# ArduinoUno_Rpi.net
KiCad netlist of a schematic drawn in Altium Designer
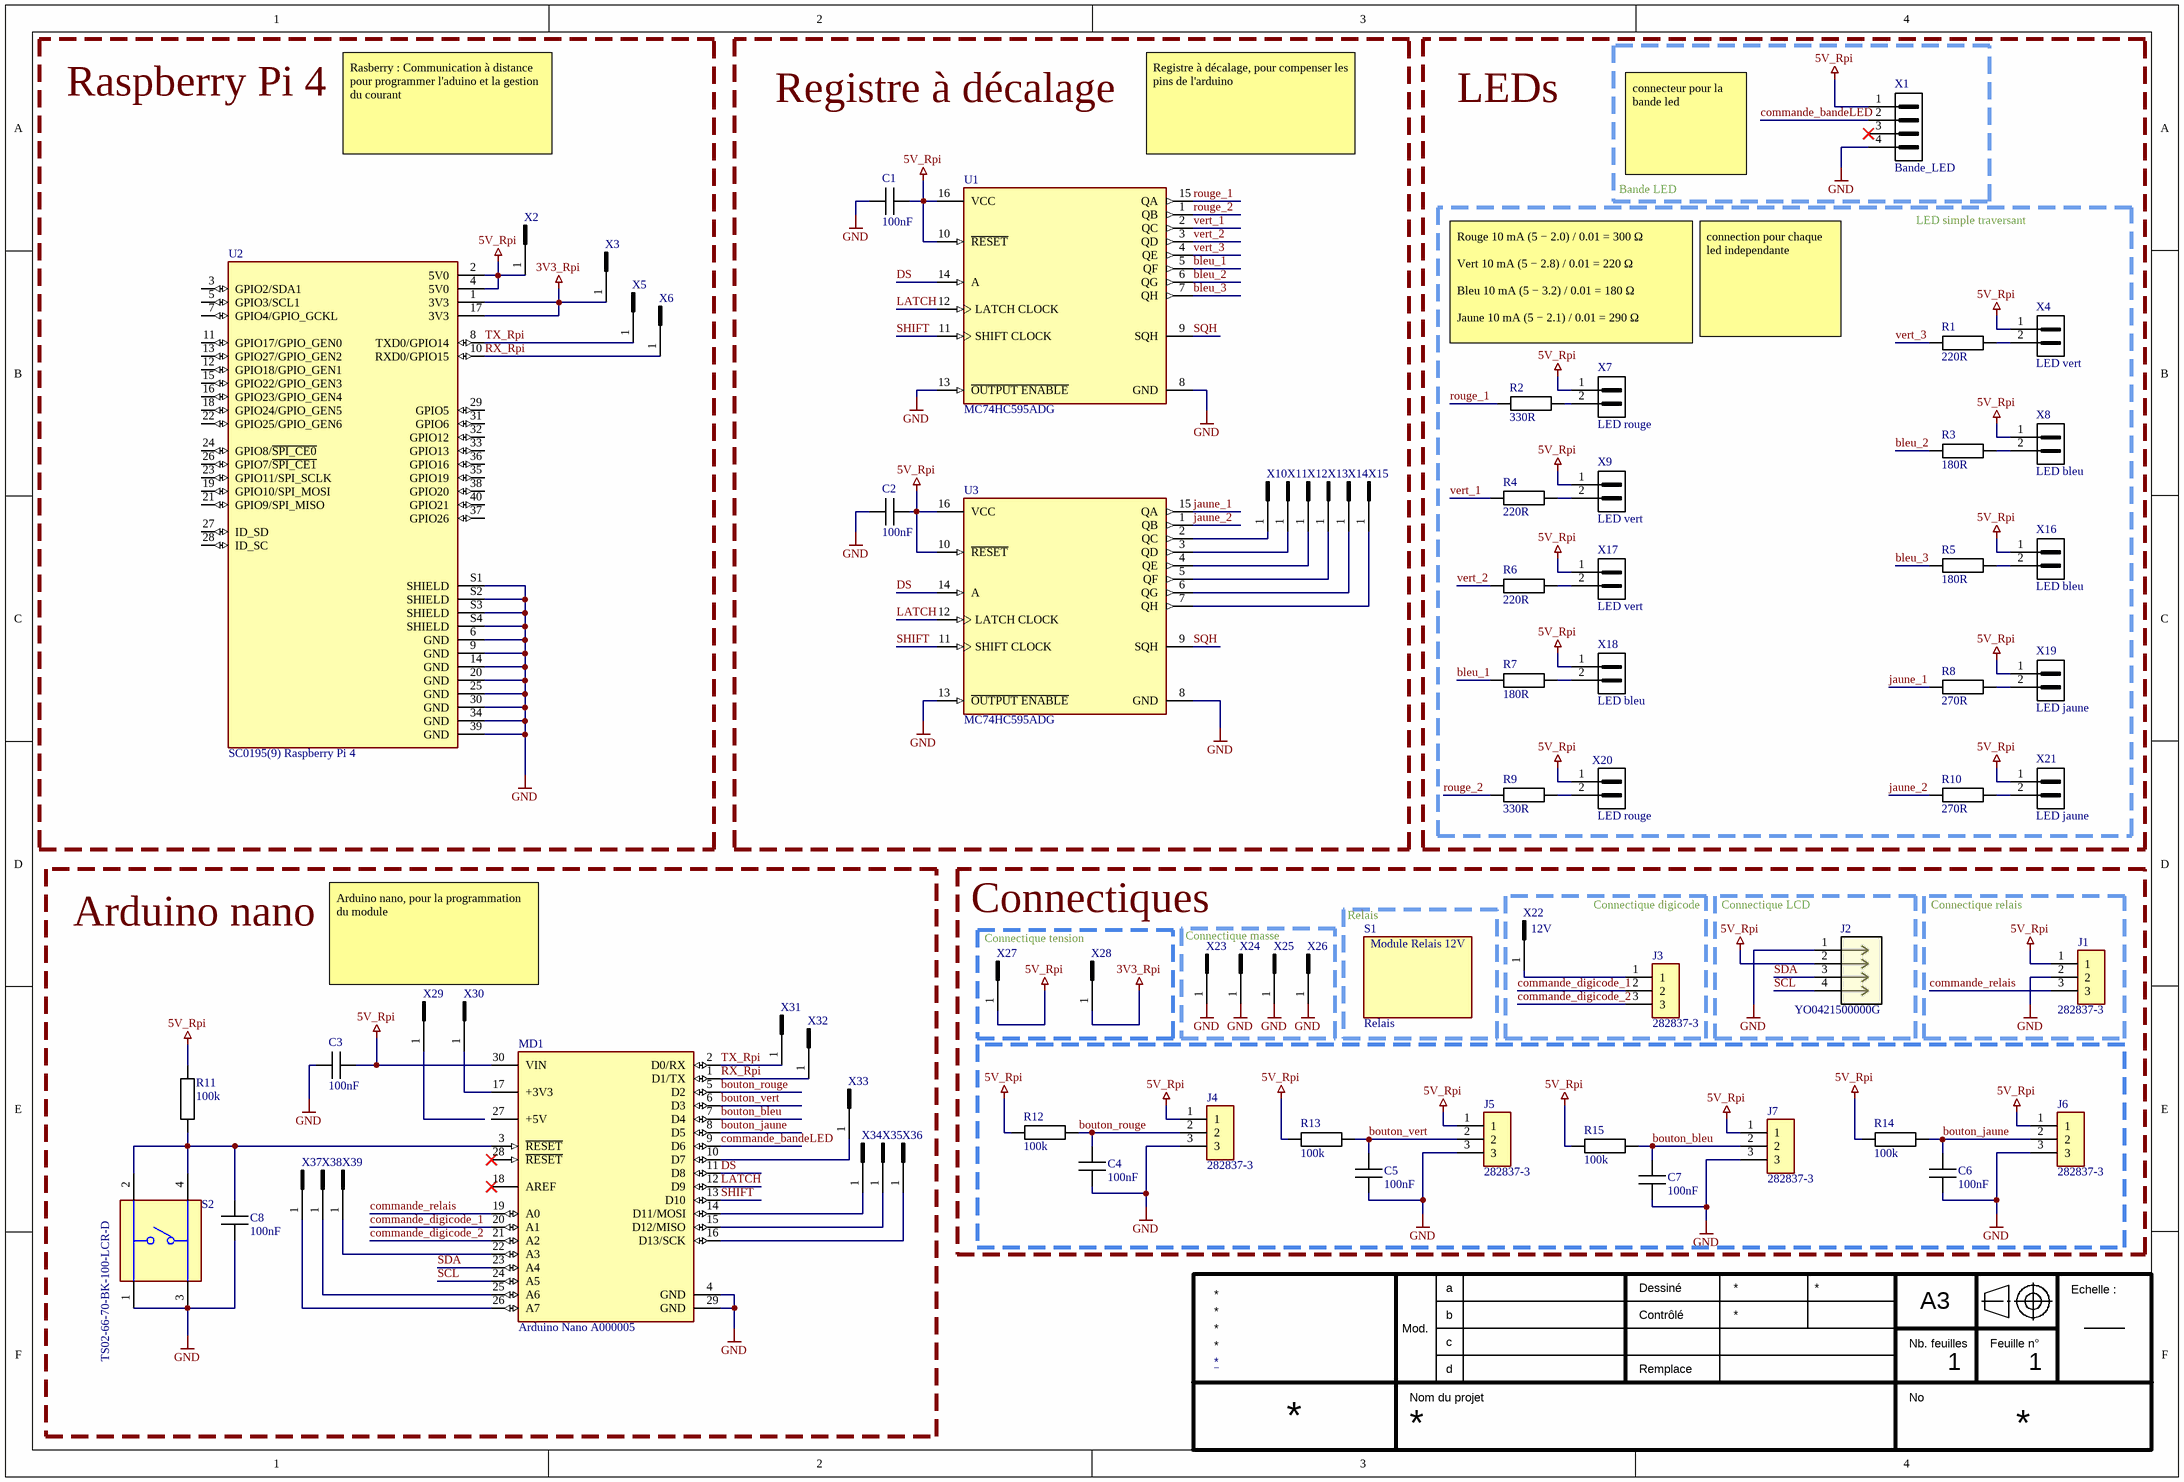
[diagram p0: ArduinoUno_Rpi.SchDoc]

(export (version "E")
  (design (tool "Eeschema 10.0.6"))
  (components
    (comp (ref "C1")
      (value "100nF")
      (footprint "CAPC2012X08M")
      (description "CAPC 100nF X7R 50V 10% 2012 (0805 INCH)")
      (fields (field (name "VOLTAGE") "50V") (field (name "MANUFACTURER") "TDK"))
      (libsource (lib "ETML-ES") (part "CAP"))
    )
    (comp (ref "C2")
      (value "100nF")
      (footprint "CAPC2012X08M")
      (description "CAPC 100nF X7R 50V 10% 2012 (0805 INCH)")
      (fields (field (name "VOLTAGE") "50V") (field (name "MANUFACTURER") "TDK"))
      (libsource (lib "ETML-ES") (part "CAP"))
    )
    (comp (ref "C3")
      (value "100nF")
      (footprint "CAPC2012X08M")
      (description "CAPC 100nF X7R 50V 10% 2012 (0805 INCH)")
      (fields (field (name "VOLTAGE") "50V") (field (name "MANUFACTURER") "TDK"))
      (libsource (lib "ETML-ES") (part "CAP"))
    )
    (comp (ref "C4")
      (value "100nF")
      (footprint "CAPC2012X08M")
      (description "CAPC 100nF X7R 50V 10% 2012 (0805 INCH)")
      (fields (field (name "VOLTAGE") "50V") (field (name "MANUFACTURER") "TDK"))
      (libsource (lib "ETML-ES") (part "CAP"))
    )
    (comp (ref "C5")
      (value "100nF")
      (footprint "CAPC2012X08M")
      (description "CAPC 100nF X7R 50V 10% 2012 (0805 INCH)")
      (fields (field (name "VOLTAGE") "50V") (field (name "MANUFACTURER") "TDK"))
      (libsource (lib "ETML-ES") (part "CAP"))
    )
    (comp (ref "C6")
      (value "100nF")
      (footprint "CAPC2012X08M")
      (description "CAPC 100nF X7R 50V 10% 2012 (0805 INCH)")
      (fields (field (name "VOLTAGE") "50V") (field (name "MANUFACTURER") "TDK"))
      (libsource (lib "ETML-ES") (part "CAP"))
    )
    (comp (ref "C7")
      (value "100nF")
      (footprint "CAPC2012X08M")
      (description "CAPC 100nF X7R 50V 10% 2012 (0805 INCH)")
      (fields (field (name "VOLTAGE") "50V") (field (name "MANUFACTURER") "TDK"))
      (libsource (lib "ETML-ES") (part "CAP"))
    )
    (comp (ref "C8")
      (value "100nF")
      (footprint "CAPC2012X08M")
      (description "CAPC 100nF X7R 50V 10% 2012 (0805 INCH)")
      (fields (field (name "VOLTAGE") "50V") (field (name "MANUFACTURER") "TDK"))
      (libsource (lib "ETML-ES") (part "CAP"))
    )
    (comp (ref "J1")
      (value "282837-3")
      (footprint "TE_282837-3")
      (description "TERMI-BLOK PCB MOUNT 3P")
      (libsource (lib "Schlib1") (part "282837-3"))
    )
    (comp (ref "J2")
      (value "YO0421500000G")
      (footprint "CONN4_500000G_AMP")
      (description "No Description Available")
      (fields (field (name "COPYRIGHT") "Copyright (C) 2025 Ultra Librarian. All rights reserved."))
      (libsource (lib "Schlib1") (part "YO0421500000G"))
    )
    (comp (ref "J3")
      (value "282837-3")
      (footprint "TE_282837-3")
      (description "TERMI-BLOK PCB MOUNT 3P")
      (libsource (lib "Schlib1") (part "282837-3"))
    )
    (comp (ref "J4")
      (value "282837-3")
      (footprint "TE_282837-3")
      (description "TERMI-BLOK PCB MOUNT 3P")
      (libsource (lib "Schlib1") (part "282837-3"))
    )
    (comp (ref "J5")
      (value "282837-3")
      (footprint "TE_282837-3")
      (description "TERMI-BLOK PCB MOUNT 3P")
      (libsource (lib "Schlib1") (part "282837-3"))
    )
    (comp (ref "J6")
      (value "282837-3")
      (footprint "TE_282837-3")
      (description "TERMI-BLOK PCB MOUNT 3P")
      (libsource (lib "Schlib1") (part "282837-3"))
    )
    (comp (ref "J7")
      (value "282837-3")
      (footprint "TE_282837-3")
      (description "TERMI-BLOK PCB MOUNT 3P")
      (libsource (lib "Schlib1") (part "282837-3"))
    )
    (comp (ref "MD1")
      (value "Arduino Nano A000005")
      (footprint "FP-A000005-MFG")
      (description "ARDUINO NANO ATMEGA328 EVAL BRD")
      (libsource (lib "Altium Content Vault") (part "d190c066e99afd1c6882cf92e11b2cc"))
    )
    (comp (ref "R1")
      (value "220R")
      (footprint "RESC1608X06M")
      (description "RES 220ohm  ±1% 0.1W  1608 (0603 INCH)")
      (fields (field (name "POWER") "0.1W") (field (name "VOLTAGE") "75V"))
      (libsource (lib "ETML-ES") (part "RES"))
    )
    (comp (ref "R2")
      (value "330R")
      (footprint "RESC1608X06M")
      (description "RES 330ohm  ±1% 0.1W  1608 (0603 INCH)")
      (fields (field (name "TOLERANCE") "±1%") (field (name "VOLTAGE") "75V"))
      (libsource (lib "ETML-ES") (part "RES"))
    )
    (comp (ref "R3")
      (value "180R")
      (footprint "RESC1608X06M")
      (description "RES 180ohm  ±1% 0.1W  1608 (0603 INCH)")
      (fields (field (name "TOLERANCE") "±1%") (field (name "VOLTAGE") "75V"))
      (libsource (lib "ETML-ES") (part "RES"))
    )
    (comp (ref "R4")
      (value "220R")
      (footprint "RESC1608X06M")
      (description "RES 220ohm  ±1% 0.1W  1608 (0603 INCH)")
      (fields (field (name "POWER") "0.1W") (field (name "VOLTAGE") "75V"))
      (libsource (lib "ETML-ES") (part "RES"))
    )
    (comp (ref "R5")
      (value "180R")
      (footprint "RESC1608X06M")
      (description "RES 180ohm  ±1% 0.1W  1608 (0603 INCH)")
      (fields (field (name "TOLERANCE") "±1%") (field (name "VOLTAGE") "75V"))
      (libsource (lib "ETML-ES") (part "RES"))
    )
    (comp (ref "R6")
      (value "220R")
      (footprint "RESC1608X06M")
      (description "RES 220ohm  ±1% 0.1W  1608 (0603 INCH)")
      (fields (field (name "POWER") "0.1W") (field (name "VOLTAGE") "75V"))
      (libsource (lib "ETML-ES") (part "RES"))
    )
    (comp (ref "R7")
      (value "180R")
      (footprint "RESC1608X06M")
      (description "RES 180ohm  ±1% 0.1W  1608 (0603 INCH)")
      (fields (field (name "TOLERANCE") "±1%") (field (name "VOLTAGE") "75V"))
      (libsource (lib "ETML-ES") (part "RES"))
    )
    (comp (ref "R8")
      (value "270R")
      (footprint "RESC1608X06M")
      (description "RES 270ohm  ±1% 0.1W  1608 (0603 INCH)")
      (fields (field (name "TOLERANCE") "±1%") (field (name "MANUFACTURER") "Yageo"))
      (libsource (lib "ETML-ES") (part "RES"))
    )
    (comp (ref "R9")
      (value "330R")
      (footprint "RESC1608X06M")
      (description "RES 330ohm  ±1% 0.1W  1608 (0603 INCH)")
      (fields (field (name "TOLERANCE") "±1%") (field (name "VOLTAGE") "75V"))
      (libsource (lib "ETML-ES") (part "RES"))
    )
    (comp (ref "R10")
      (value "270R")
      (footprint "RESC1608X06M")
      (description "RES 270ohm  ±1% 0.1W  1608 (0603 INCH)")
      (fields (field (name "TOLERANCE") "±1%") (field (name "MANUFACTURER") "Yageo"))
      (libsource (lib "ETML-ES") (part "RES"))
    )
    (comp (ref "R11")
      (value "100k")
      (footprint "RESC2012X06M")
      (description "RES 100kohm  ±1% 0.125W 2012 (0805 INCH)")
      (fields (field (name "MANUFACTURER") "Yageo") (field (name "VOLTAGE") "150V"))
      (libsource (lib "ETML-ES") (part "RES"))
    )
    (comp (ref "R12")
      (value "100k")
      (footprint "RESC2012X06M")
      (description "RES 100kohm  ±1% 0.125W 2012 (0805 INCH)")
      (fields (field (name "MANUFACTURER") "Yageo") (field (name "VOLTAGE") "150V"))
      (libsource (lib "ETML-ES") (part "RES"))
    )
    (comp (ref "R13")
      (value "100k")
      (footprint "RESC2012X06M")
      (description "RES 100kohm  ±1% 0.125W 2012 (0805 INCH)")
      (fields (field (name "MANUFACTURER") "Yageo") (field (name "VOLTAGE") "150V"))
      (libsource (lib "ETML-ES") (part "RES"))
    )
    (comp (ref "R14")
      (value "100k")
      (footprint "RESC2012X06M")
      (description "RES 100kohm  ±1% 0.125W 2012 (0805 INCH)")
      (fields (field (name "MANUFACTURER") "Yageo") (field (name "VOLTAGE") "150V"))
      (libsource (lib "ETML-ES") (part "RES"))
    )
    (comp (ref "R15")
      (value "100k")
      (footprint "RESC2012X06M")
      (description "RES 100kohm  ±1% 0.125W 2012 (0805 INCH)")
      (fields (field (name "MANUFACTURER") "Yageo") (field (name "VOLTAGE") "150V"))
      (libsource (lib "ETML-ES") (part "RES"))
    )
    (comp (ref "S1")
      (value "Relais")
      (footprint "BOOSTER12V")
      (description "6 x 6 mm, 7 mm Actuator Height, 100 gf, Black, Long Crimped, Through Hole, SPST, Tactile Switch")
      (fields (field (name "MF") "Same Sky") (field (name "MP") "TS02-66-70-BK-100-LCR-D"))
      (libsource (lib "Schlib1") (part "Relais"))
    )
    (comp (ref "S2")
      (value "TS02-66-70-BK-100-LCR-D")
      (footprint "SW_TS02-66-70-BK-100-LCR-D")
      (description "6 x 6 mm, 7 mm Actuator Height, 100 gf, Black, Long Crimped, Through Hole, SPST, Tactile Switch")
      (fields (field (name "MF") "Same Sky"))
      (libsource (lib "Schlib1") (part "TS02-66-70-BK-100-LCR-D"))
    )
    (comp (ref "U1")
      (value "MC74HC595ADG")
      (footprint "FP-751B-05-MFG")
      (description "IC SHIFT REGISTER 8BIT 16-SOIC")
      (fields
        (field (name "MANUFACTURER") "On Semiconductor")
        (field (name "OCTOPART") "https://octopart.com/mc74hc595adg-on+semiconductor-127876")
      )
      (libsource (lib "Altium Content Vault") (part "e046d8e229ee38add04da4060949ea7"))
    )
    (comp (ref "U2")
      (value "SC0195(9) Raspberry Pi 4")
      (footprint "MODULE_SC0195(9)")
      (fields (field (name "MF") "Raspberry Pi") (field (name "MP") "SC0195(9)"))
      (libsource (lib "Schlib1") (part "SC0195(9)"))
    )
    (comp (ref "U3")
      (value "MC74HC595ADG")
      (footprint "FP-751B-05-MFG")
      (description "IC SHIFT REGISTER 8BIT 16-SOIC")
      (fields
        (field (name "MANUFACTURER") "On Semiconductor")
        (field (name "OCTOPART") "https://octopart.com/mc74hc595adg-on+semiconductor-127876")
      )
      (libsource (lib "Altium Content Vault") (part "e046d8e229ee38add04da4060949ea7"))
    )
    (comp (ref "X1")
      (value "Bande_LED")
      (footprint "PIN-1x04-2.54")
      (description "PIN HEADER 2.54 1x04")
      (fields (field (name "MANUFACTURER") "Würth Electronik") (field (name "VOLTAGE") "250V"))
      (libsource (lib "ETML-ES") (part "CON-PIN-1x04"))
    )
    (comp (ref "X2")
      (value "2.54")
      (footprint "PIN-1x01-2.54")
      (description "PIN HEADER 2.54 1x01")
      (fields (field (name "VOLTAGE") "250V") (field (name "MANUFACTURER") "Würth Electronik"))
      (libsource (lib "ETML-ES") (part "CON-PIN-1x01"))
    )
    (comp (ref "X3")
      (value "2.54")
      (footprint "PIN-1x01-2.54")
      (description "PIN HEADER 2.54 1x01")
      (fields (field (name "VOLTAGE") "250V") (field (name "MANUFACTURER") "Würth Electronik"))
      (libsource (lib "ETML-ES") (part "CON-PIN-1x01"))
    )
    (comp (ref "X4")
      (value "LED vert")
      (footprint "PIN-1x02-2.54")
      (description "PIN HEADER 2.54 1x02")
      (fields (field (name "MANUFACTURER") "Würth Electronik") (field (name "VOLTAGE") "250V"))
      (libsource (lib "ETML-ES") (part "CON-PIN-1x02"))
    )
    (comp (ref "X5")
      (value "2.54")
      (footprint "PIN-1x01-2.54")
      (description "PIN HEADER 2.54 1x01")
      (fields (field (name "VOLTAGE") "250V") (field (name "MANUFACTURER") "Würth Electronik"))
      (libsource (lib "ETML-ES") (part "CON-PIN-1x01"))
    )
    (comp (ref "X6")
      (value "2.54")
      (footprint "PIN-1x01-2.54")
      (description "PIN HEADER 2.54 1x01")
      (fields (field (name "VOLTAGE") "250V") (field (name "MANUFACTURER") "Würth Electronik"))
      (libsource (lib "ETML-ES") (part "CON-PIN-1x01"))
    )
    (comp (ref "X7")
      (value "LED rouge")
      (footprint "PIN-1x02-2.54")
      (description "PIN HEADER 2.54 1x02")
      (fields (field (name "MANUFACTURER") "Würth Electronik") (field (name "VOLTAGE") "250V"))
      (libsource (lib "ETML-ES") (part "CON-PIN-1x02"))
    )
    (comp (ref "X8")
      (value "LED bleu")
      (footprint "PIN-1x02-2.54")
      (description "PIN HEADER 2.54 1x02")
      (fields (field (name "MANUFACTURER") "Würth Electronik") (field (name "VOLTAGE") "250V"))
      (libsource (lib "ETML-ES") (part "CON-PIN-1x02"))
    )
    (comp (ref "X9")
      (value "LED vert")
      (footprint "PIN-1x02-2.54")
      (description "PIN HEADER 2.54 1x02")
      (fields (field (name "MANUFACTURER") "Würth Electronik") (field (name "VOLTAGE") "250V"))
      (libsource (lib "ETML-ES") (part "CON-PIN-1x02"))
    )
    (comp (ref "X10")
      (value "2.54")
      (footprint "PIN-1x01-2.54")
      (description "PIN HEADER 2.54 1x01")
      (fields (field (name "VOLTAGE") "250V") (field (name "MANUFACTURER") "Würth Electronik"))
      (libsource (lib "ETML-ES") (part "CON-PIN-1x01"))
    )
    (comp (ref "X11")
      (value "2.54")
      (footprint "PIN-1x01-2.54")
      (description "PIN HEADER 2.54 1x01")
      (fields (field (name "VOLTAGE") "250V") (field (name "MANUFACTURER") "Würth Electronik"))
      (libsource (lib "ETML-ES") (part "CON-PIN-1x01"))
    )
    (comp (ref "X12")
      (value "2.54")
      (footprint "PIN-1x01-2.54")
      (description "PIN HEADER 2.54 1x01")
      (fields (field (name "VOLTAGE") "250V") (field (name "MANUFACTURER") "Würth Electronik"))
      (libsource (lib "ETML-ES") (part "CON-PIN-1x01"))
    )
    (comp (ref "X13")
      (value "2.54")
      (footprint "PIN-1x01-2.54")
      (description "PIN HEADER 2.54 1x01")
      (fields (field (name "VOLTAGE") "250V") (field (name "MANUFACTURER") "Würth Electronik"))
      (libsource (lib "ETML-ES") (part "CON-PIN-1x01"))
    )
    (comp (ref "X14")
      (value "2.54")
      (footprint "PIN-1x01-2.54")
      (description "PIN HEADER 2.54 1x01")
      (fields (field (name "VOLTAGE") "250V") (field (name "MANUFACTURER") "Würth Electronik"))
      (libsource (lib "ETML-ES") (part "CON-PIN-1x01"))
    )
    (comp (ref "X15")
      (value "2.54")
      (footprint "PIN-1x01-2.54")
      (description "PIN HEADER 2.54 1x01")
      (fields (field (name "VOLTAGE") "250V") (field (name "MANUFACTURER") "Würth Electronik"))
      (libsource (lib "ETML-ES") (part "CON-PIN-1x01"))
    )
    (comp (ref "X16")
      (value "LED bleu")
      (footprint "PIN-1x02-2.54")
      (description "PIN HEADER 2.54 1x02")
      (fields (field (name "MANUFACTURER") "Würth Electronik") (field (name "VOLTAGE") "250V"))
      (libsource (lib "ETML-ES") (part "CON-PIN-1x02"))
    )
    (comp (ref "X17")
      (value "LED vert")
      (footprint "PIN-1x02-2.54")
      (description "PIN HEADER 2.54 1x02")
      (fields (field (name "MANUFACTURER") "Würth Electronik") (field (name "VOLTAGE") "250V"))
      (libsource (lib "ETML-ES") (part "CON-PIN-1x02"))
    )
    (comp (ref "X18")
      (value "LED bleu")
      (footprint "PIN-1x02-2.54")
      (description "PIN HEADER 2.54 1x02")
      (fields (field (name "MANUFACTURER") "Würth Electronik") (field (name "VOLTAGE") "250V"))
      (libsource (lib "ETML-ES") (part "CON-PIN-1x02"))
    )
    (comp (ref "X19")
      (value "LED jaune")
      (footprint "PIN-1x02-2.54")
      (description "PIN HEADER 2.54 1x02")
      (fields (field (name "MANUFACTURER") "Würth Electronik") (field (name "VOLTAGE") "250V"))
      (libsource (lib "ETML-ES") (part "CON-PIN-1x02"))
    )
    (comp (ref "X20")
      (value "LED rouge")
      (footprint "PIN-1x02-2.54")
      (description "PIN HEADER 2.54 1x02")
      (fields (field (name "MANUFACTURER") "Würth Electronik") (field (name "VOLTAGE") "250V"))
      (libsource (lib "ETML-ES") (part "CON-PIN-1x02"))
    )
    (comp (ref "X21")
      (value "LED jaune")
      (footprint "PIN-1x02-2.54")
      (description "PIN HEADER 2.54 1x02")
      (fields (field (name "MANUFACTURER") "Würth Electronik") (field (name "VOLTAGE") "250V"))
      (libsource (lib "ETML-ES") (part "CON-PIN-1x02"))
    )
    (comp (ref "X22")
      (value "12V")
      (footprint "PIN-1x01-2.54")
      (description "PIN HEADER 2.54 1x01")
      (fields (field (name "VOLTAGE") "250V") (field (name "MANUFACTURER") "Würth Electronik"))
      (libsource (lib "ETML-ES") (part "CON-PIN-1x01"))
    )
    (comp (ref "X23")
      (value "2.54")
      (footprint "PIN-1x01-2.54")
      (description "PIN HEADER 2.54 1x01")
      (fields (field (name "VOLTAGE") "250V") (field (name "MANUFACTURER") "Würth Electronik"))
      (libsource (lib "ETML-ES") (part "CON-PIN-1x01"))
    )
    (comp (ref "X24")
      (value "2.54")
      (footprint "PIN-1x01-2.54")
      (description "PIN HEADER 2.54 1x01")
      (fields (field (name "VOLTAGE") "250V") (field (name "MANUFACTURER") "Würth Electronik"))
      (libsource (lib "ETML-ES") (part "CON-PIN-1x01"))
    )
    (comp (ref "X25")
      (value "2.54")
      (footprint "PIN-1x01-2.54")
      (description "PIN HEADER 2.54 1x01")
      (fields (field (name "VOLTAGE") "250V") (field (name "MANUFACTURER") "Würth Electronik"))
      (libsource (lib "ETML-ES") (part "CON-PIN-1x01"))
    )
    (comp (ref "X26")
      (value "2.54")
      (footprint "PIN-1x01-2.54")
      (description "PIN HEADER 2.54 1x01")
      (fields (field (name "VOLTAGE") "250V") (field (name "MANUFACTURER") "Würth Electronik"))
      (libsource (lib "ETML-ES") (part "CON-PIN-1x01"))
    )
    (comp (ref "X27")
      (value "2.54")
      (footprint "PIN-1x01-2.54")
      (description "PIN HEADER 2.54 1x01")
      (fields (field (name "VOLTAGE") "250V") (field (name "MANUFACTURER") "Würth Electronik"))
      (libsource (lib "ETML-ES") (part "CON-PIN-1x01"))
    )
    (comp (ref "X28")
      (value "2.54")
      (footprint "PIN-1x01-2.54")
      (description "PIN HEADER 2.54 1x01")
      (fields (field (name "VOLTAGE") "250V") (field (name "MANUFACTURER") "Würth Electronik"))
      (libsource (lib "ETML-ES") (part "CON-PIN-1x01"))
    )
    (comp (ref "X29")
      (value "2.54")
      (footprint "PIN-1x01-2.54")
      (description "PIN HEADER 2.54 1x01")
      (fields (field (name "VOLTAGE") "250V") (field (name "MANUFACTURER") "Würth Electronik"))
      (libsource (lib "ETML-ES") (part "CON-PIN-1x01"))
    )
    (comp (ref "X30")
      (value "2.54")
      (footprint "PIN-1x01-2.54")
      (description "PIN HEADER 2.54 1x01")
      (fields (field (name "VOLTAGE") "250V") (field (name "MANUFACTURER") "Würth Electronik"))
      (libsource (lib "ETML-ES") (part "CON-PIN-1x01"))
    )
    (comp (ref "X31")
      (value "2.54")
      (footprint "PIN-1x01-2.54")
      (description "PIN HEADER 2.54 1x01")
      (fields (field (name "VOLTAGE") "250V") (field (name "MANUFACTURER") "Würth Electronik"))
      (libsource (lib "ETML-ES") (part "CON-PIN-1x01"))
    )
    (comp (ref "X32")
      (value "2.54")
      (footprint "PIN-1x01-2.54")
      (description "PIN HEADER 2.54 1x01")
      (fields (field (name "VOLTAGE") "250V") (field (name "MANUFACTURER") "Würth Electronik"))
      (libsource (lib "ETML-ES") (part "CON-PIN-1x01"))
    )
    (comp (ref "X33")
      (value "2.54")
      (footprint "PIN-1x01-2.54")
      (description "PIN HEADER 2.54 1x01")
      (fields (field (name "VOLTAGE") "250V") (field (name "MANUFACTURER") "Würth Electronik"))
      (libsource (lib "ETML-ES") (part "CON-PIN-1x01"))
    )
    (comp (ref "X34")
      (value "2.54")
      (footprint "PIN-1x01-2.54")
      (description "PIN HEADER 2.54 1x01")
      (fields (field (name "VOLTAGE") "250V") (field (name "MANUFACTURER") "Würth Electronik"))
      (libsource (lib "ETML-ES") (part "CON-PIN-1x01"))
    )
    (comp (ref "X35")
      (value "2.54")
      (footprint "PIN-1x01-2.54")
      (description "PIN HEADER 2.54 1x01")
      (fields (field (name "VOLTAGE") "250V") (field (name "MANUFACTURER") "Würth Electronik"))
      (libsource (lib "ETML-ES") (part "CON-PIN-1x01"))
    )
    (comp (ref "X36")
      (value "2.54")
      (footprint "PIN-1x01-2.54")
      (description "PIN HEADER 2.54 1x01")
      (fields (field (name "VOLTAGE") "250V") (field (name "MANUFACTURER") "Würth Electronik"))
      (libsource (lib "ETML-ES") (part "CON-PIN-1x01"))
    )
    (comp (ref "X37")
      (value "2.54")
      (footprint "PIN-1x01-2.54")
      (description "PIN HEADER 2.54 1x01")
      (fields (field (name "VOLTAGE") "250V") (field (name "MANUFACTURER") "Würth Electronik"))
      (libsource (lib "ETML-ES") (part "CON-PIN-1x01"))
    )
    (comp (ref "X38")
      (value "2.54")
      (footprint "PIN-1x01-2.54")
      (description "PIN HEADER 2.54 1x01")
      (fields (field (name "VOLTAGE") "250V") (field (name "MANUFACTURER") "Würth Electronik"))
      (libsource (lib "ETML-ES") (part "CON-PIN-1x01"))
    )
    (comp (ref "X39")
      (value "2.54")
      (footprint "PIN-1x01-2.54")
      (description "PIN HEADER 2.54 1x01")
      (fields (field (name "VOLTAGE") "250V") (field (name "MANUFACTURER") "Würth Electronik"))
      (libsource (lib "ETML-ES") (part "CON-PIN-1x01"))
    )
  )
  (nets
    (net (code "1") (name "/DS") (class "Default")
      (node (ref "MD1") (pin "11") (pinfunction "D8_11") (pintype "bidirectional"))
      (node (ref "U1") (pin "14") (pinfunction "A_14") (pintype "input"))
      (node (ref "U3") (pin "14") (pinfunction "A_14") (pintype "input"))
    )
    (net (code "2") (name "/LATCH") (class "Default")
      (node (ref "MD1") (pin "12") (pinfunction "D9_12") (pintype "bidirectional"))
      (node (ref "U1") (pin "12") (pinfunction "LATCH_CLOCK_12") (pintype "input"))
      (node (ref "U3") (pin "12") (pinfunction "LATCH_CLOCK_12") (pintype "input"))
    )
    (net (code "3") (name "/RX_Rpi") (class "Default")
      (node (ref "MD1") (pin "1") (pinfunction "D1/TX_1") (pintype "bidirectional"))
      (node (ref "U2") (pin "10") (pinfunction "RXD0/GPIO15_10") (pintype "bidirectional"))
      (node (ref "X32") (pin "1") (pinfunction "1_1") (pintype "passive"))
      (node (ref "X6") (pin "1") (pinfunction "1_1") (pintype "passive"))
    )
    (net (code "4") (name "/SCL") (class "Default")
      (node (ref "J2") (pin "4") (pinfunction "4_4") (pintype "passive"))
      (node (ref "MD1") (pin "24") (pinfunction "A5_24") (pintype "bidirectional"))
    )
    (net (code "5") (name "/SDA") (class "Default")
      (node (ref "J2") (pin "3") (pinfunction "3_3") (pintype "passive"))
      (node (ref "MD1") (pin "23") (pinfunction "A4_23") (pintype "bidirectional"))
    )
    (net (code "6") (name "/SHIFT") (class "Default")
      (node (ref "MD1") (pin "13") (pinfunction "D10_13") (pintype "bidirectional"))
      (node (ref "U1") (pin "11") (pinfunction "SHIFT_CLOCK_11") (pintype "input"))
      (node (ref "U3") (pin "11") (pinfunction "SHIFT_CLOCK_11") (pintype "input"))
    )
    (net (code "7") (name "/SQH") (class "Default")
      (node (ref "U1") (pin "9") (pinfunction "SQH_9") (pintype "passive"))
      (node (ref "U3") (pin "9") (pinfunction "SQH_9") (pintype "passive"))
    )
    (net (code "8") (name "/TX_Rpi") (class "Default")
      (node (ref "MD1") (pin "2") (pinfunction "D0/RX_2") (pintype "bidirectional"))
      (node (ref "U2") (pin "8") (pinfunction "TXD0/GPIO14_8") (pintype "bidirectional"))
      (node (ref "X31") (pin "1") (pinfunction "1_1") (pintype "passive"))
      (node (ref "X5") (pin "1") (pinfunction "1_1") (pintype "passive"))
    )
    (net (code "9") (name "/bleu_1") (class "Default")
      (node (ref "R7") (pin "1") (pinfunction "1_1") (pintype "passive"))
      (node (ref "U1") (pin "5") (pinfunction "QF_5") (pintype "output"))
    )
    (net (code "10") (name "/bleu_2") (class "Default")
      (node (ref "R3") (pin "1") (pinfunction "1_1") (pintype "passive"))
      (node (ref "U1") (pin "6") (pinfunction "QG_6") (pintype "output"))
    )
    (net (code "11") (name "/bleu_3") (class "Default")
      (node (ref "R5") (pin "1") (pinfunction "1_1") (pintype "passive"))
      (node (ref "U1") (pin "7") (pinfunction "QH_7") (pintype "output"))
    )
    (net (code "12") (name "/bouton_bleu") (class "Default")
      (node (ref "C7") (pin "2") (pinfunction "2_2") (pintype "passive"))
      (node (ref "J7") (pin "2") (pinfunction "2_2") (pintype "passive"))
      (node (ref "MD1") (pin "7") (pinfunction "D4_7") (pintype "bidirectional"))
      (node (ref "R15") (pin "1") (pinfunction "1_1") (pintype "passive"))
    )
    (net (code "13") (name "/bouton_jaune") (class "Default")
      (node (ref "C6") (pin "2") (pinfunction "2_2") (pintype "passive"))
      (node (ref "J6") (pin "2") (pinfunction "2_2") (pintype "passive"))
      (node (ref "MD1") (pin "8") (pinfunction "D5_8") (pintype "bidirectional"))
      (node (ref "R14") (pin "1") (pinfunction "1_1") (pintype "passive"))
    )
    (net (code "14") (name "/bouton_rouge") (class "Default")
      (node (ref "C4") (pin "2") (pinfunction "2_2") (pintype "passive"))
      (node (ref "J4") (pin "2") (pinfunction "2_2") (pintype "passive"))
      (node (ref "MD1") (pin "5") (pinfunction "D2_5") (pintype "bidirectional"))
      (node (ref "R12") (pin "1") (pinfunction "1_1") (pintype "passive"))
    )
    (net (code "15") (name "/bouton_vert") (class "Default")
      (node (ref "C5") (pin "2") (pinfunction "2_2") (pintype "passive"))
      (node (ref "J5") (pin "2") (pinfunction "2_2") (pintype "passive"))
      (node (ref "MD1") (pin "6") (pinfunction "D3_6") (pintype "bidirectional"))
      (node (ref "R13") (pin "1") (pinfunction "1_1") (pintype "passive"))
    )
    (net (code "16") (name "/commande_bandeLED") (class "Default")
      (node (ref "MD1") (pin "9") (pinfunction "D6_9") (pintype "bidirectional"))
      (node (ref "X1") (pin "2") (pinfunction "2_2") (pintype "passive"))
    )
    (net (code "17") (name "/commande_digicode_1") (class "Default")
      (node (ref "J3") (pin "2") (pinfunction "2_2") (pintype "passive"))
      (node (ref "MD1") (pin "20") (pinfunction "A1_20") (pintype "bidirectional"))
    )
    (net (code "18") (name "/commande_digicode_2") (class "Default")
      (node (ref "J3") (pin "3") (pinfunction "3_3") (pintype "passive"))
      (node (ref "MD1") (pin "21") (pinfunction "A2_21") (pintype "bidirectional"))
    )
    (net (code "19") (name "/commande_relais") (class "Default")
      (node (ref "J1") (pin "3") (pinfunction "3_3") (pintype "passive"))
      (node (ref "MD1") (pin "19") (pinfunction "A0_19") (pintype "bidirectional"))
    )
    (net (code "20") (name "/jaune_1") (class "Default")
      (node (ref "R8") (pin "1") (pinfunction "1_1") (pintype "passive"))
      (node (ref "U3") (pin "15") (pinfunction "QA_15") (pintype "output"))
    )
    (net (code "21") (name "/jaune_2") (class "Default")
      (node (ref "R10") (pin "1") (pinfunction "1_1") (pintype "passive"))
      (node (ref "U3") (pin "1") (pinfunction "QB_1") (pintype "output"))
    )
    (net (code "22") (name "/rouge_1") (class "Default")
      (node (ref "R2") (pin "1") (pinfunction "1_1") (pintype "passive"))
      (node (ref "U1") (pin "15") (pinfunction "QA_15") (pintype "output"))
    )
    (net (code "23") (name "/rouge_2") (class "Default")
      (node (ref "R9") (pin "1") (pinfunction "1_1") (pintype "passive"))
      (node (ref "U1") (pin "1") (pinfunction "QB_1") (pintype "output"))
    )
    (net (code "24") (name "/vert_1") (class "Default")
      (node (ref "R4") (pin "1") (pinfunction "1_1") (pintype "passive"))
      (node (ref "U1") (pin "2") (pinfunction "QC_2") (pintype "output"))
    )
    (net (code "25") (name "/vert_2") (class "Default")
      (node (ref "R6") (pin "1") (pinfunction "1_1") (pintype "passive"))
      (node (ref "U1") (pin "3") (pinfunction "QD_3") (pintype "output"))
    )
    (net (code "26") (name "/vert_3") (class "Default")
      (node (ref "R1") (pin "1") (pinfunction "1_1") (pintype "passive"))
      (node (ref "U1") (pin "4") (pinfunction "QE_4") (pintype "output"))
    )
    (net (code "27") (name "3V3_Rpi") (class "Default")
      (node (ref "U2") (pin "1") (pinfunction "3V3_1") (pintype "power_in"))
      (node (ref "U2") (pin "17") (pinfunction "3V3_17") (pintype "power_in"))
      (node (ref "X28") (pin "1") (pinfunction "1_1") (pintype "passive"))
      (node (ref "X3") (pin "1") (pinfunction "1_1") (pintype "passive"))
    )
    (net (code "28") (name "5V_Rpi") (class "Default")
      (node (ref "C1") (pin "1") (pinfunction "1_1") (pintype "passive"))
      (node (ref "C2") (pin "1") (pinfunction "1_1") (pintype "passive"))
      (node (ref "C3") (pin "1") (pinfunction "1_1") (pintype "passive"))
      (node (ref "J1") (pin "1") (pinfunction "1_1") (pintype "passive"))
      (node (ref "J2") (pin "2") (pinfunction "2_2") (pintype "passive"))
      (node (ref "J4") (pin "1") (pinfunction "1_1") (pintype "passive"))
      (node (ref "J5") (pin "1") (pinfunction "1_1") (pintype "passive"))
      (node (ref "J6") (pin "1") (pinfunction "1_1") (pintype "passive"))
      (node (ref "J7") (pin "1") (pinfunction "1_1") (pintype "passive"))
      (node (ref "MD1") (pin "30") (pinfunction "VIN_30") (pintype "power_in"))
      (node (ref "R11") (pin "2") (pinfunction "2_2") (pintype "passive"))
      (node (ref "R12") (pin "2") (pinfunction "2_2") (pintype "passive"))
      (node (ref "R13") (pin "2") (pinfunction "2_2") (pintype "passive"))
      (node (ref "R14") (pin "2") (pinfunction "2_2") (pintype "passive"))
      (node (ref "R15") (pin "2") (pinfunction "2_2") (pintype "passive"))
      (node (ref "U1") (pin "10") (pinfunction "~{RESET}_10") (pintype "input"))
      (node (ref "U1") (pin "16") (pinfunction "VCC_16") (pintype "power_in"))
      (node (ref "U2") (pin "2") (pinfunction "5V0_2") (pintype "power_in"))
      (node (ref "U2") (pin "4") (pinfunction "5V0_4") (pintype "power_in"))
      (node (ref "U3") (pin "10") (pinfunction "~{RESET}_10") (pintype "input"))
      (node (ref "U3") (pin "16") (pinfunction "VCC_16") (pintype "power_in"))
      (node (ref "X1") (pin "1") (pinfunction "1_1") (pintype "passive"))
      (node (ref "X16") (pin "1") (pinfunction "1_1") (pintype "passive"))
      (node (ref "X17") (pin "1") (pinfunction "1_1") (pintype "passive"))
      (node (ref "X18") (pin "1") (pinfunction "1_1") (pintype "passive"))
      (node (ref "X19") (pin "1") (pinfunction "1_1") (pintype "passive"))
      (node (ref "X2") (pin "1") (pinfunction "1_1") (pintype "passive"))
      (node (ref "X20") (pin "1") (pinfunction "1_1") (pintype "passive"))
      (node (ref "X21") (pin "1") (pinfunction "1_1") (pintype "passive"))
      (node (ref "X27") (pin "1") (pinfunction "1_1") (pintype "passive"))
      (node (ref "X4") (pin "1") (pinfunction "1_1") (pintype "passive"))
      (node (ref "X7") (pin "1") (pinfunction "1_1") (pintype "passive"))
      (node (ref "X8") (pin "1") (pinfunction "1_1") (pintype "passive"))
      (node (ref "X9") (pin "1") (pinfunction "1_1") (pintype "passive"))
    )
    (net (code "29") (name "GND") (class "Default")
      (node (ref "C1") (pin "2") (pinfunction "2_2") (pintype "passive"))
      (node (ref "C2") (pin "2") (pinfunction "2_2") (pintype "passive"))
      (node (ref "C3") (pin "2") (pinfunction "2_2") (pintype "passive"))
      (node (ref "C4") (pin "1") (pinfunction "1_1") (pintype "passive"))
      (node (ref "C5") (pin "1") (pinfunction "1_1") (pintype "passive"))
      (node (ref "C6") (pin "1") (pinfunction "1_1") (pintype "passive"))
      (node (ref "C7") (pin "1") (pinfunction "1_1") (pintype "passive"))
      (node (ref "C8") (pin "1") (pinfunction "1_1") (pintype "passive"))
      (node (ref "J1") (pin "2") (pinfunction "2_2") (pintype "passive"))
      (node (ref "J2") (pin "1") (pinfunction "1_1") (pintype "passive"))
      (node (ref "J4") (pin "3") (pinfunction "3_3") (pintype "passive"))
      (node (ref "J5") (pin "3") (pinfunction "3_3") (pintype "passive"))
      (node (ref "J6") (pin "3") (pinfunction "3_3") (pintype "passive"))
      (node (ref "J7") (pin "3") (pinfunction "3_3") (pintype "passive"))
      (node (ref "MD1") (pin "29") (pinfunction "GND_29") (pintype "power_in"))
      (node (ref "MD1") (pin "4") (pinfunction "GND_4") (pintype "power_in"))
      (node (ref "S2") (pin "1") (pinfunction "1_1") (pintype "passive"))
      (node (ref "S2") (pin "3") (pinfunction "3_3") (pintype "passive"))
      (node (ref "U1") (pin "13") (pinfunction "~{OUTPUT_ENABLE}_13") (pintype "input"))
      (node (ref "U1") (pin "8") (pinfunction "GND_8") (pintype "power_in"))
      (node (ref "U2") (pin "14") (pinfunction "GND_14") (pintype "power_in"))
      (node (ref "U2") (pin "20") (pinfunction "GND_20") (pintype "power_in"))
      (node (ref "U2") (pin "25") (pinfunction "GND_25") (pintype "power_in"))
      (node (ref "U2") (pin "30") (pinfunction "GND_30") (pintype "power_in"))
      (node (ref "U2") (pin "34") (pinfunction "GND_34") (pintype "power_in"))
      (node (ref "U2") (pin "39") (pinfunction "GND_39") (pintype "power_in"))
      (node (ref "U2") (pin "6") (pinfunction "GND_6") (pintype "power_in"))
      (node (ref "U2") (pin "9") (pinfunction "GND_9") (pintype "power_in"))
      (node (ref "U2") (pin "S1") (pinfunction "SHIELD_S1") (pintype "power_in"))
      (node (ref "U2") (pin "S2") (pinfunction "SHIELD_S2") (pintype "power_in"))
      (node (ref "U2") (pin "S3") (pinfunction "SHIELD_S3") (pintype "power_in"))
      (node (ref "U2") (pin "S4") (pinfunction "SHIELD_S4") (pintype "power_in"))
      (node (ref "U3") (pin "13") (pinfunction "~{OUTPUT_ENABLE}_13") (pintype "input"))
      (node (ref "U3") (pin "8") (pinfunction "GND_8") (pintype "power_in"))
      (node (ref "X1") (pin "4") (pinfunction "4_4") (pintype "passive"))
      (node (ref "X23") (pin "1") (pinfunction "1_1") (pintype "passive"))
      (node (ref "X24") (pin "1") (pinfunction "1_1") (pintype "passive"))
      (node (ref "X25") (pin "1") (pinfunction "1_1") (pintype "passive"))
      (node (ref "X26") (pin "1") (pinfunction "1_1") (pintype "passive"))
    )
    (net (code "30") (name "Net-(C8-Pad2)") (class "Default")
      (node (ref "C8") (pin "2") (pinfunction "2_2") (pintype "passive"))
      (node (ref "MD1") (pin "3") (pinfunction "~{RESET}_3") (pintype "input"))
      (node (ref "R11") (pin "1") (pinfunction "1_1") (pintype "passive"))
      (node (ref "S2") (pin "2") (pinfunction "2_2") (pintype "passive"))
      (node (ref "S2") (pin "4") (pinfunction "4_4") (pintype "passive"))
    )
    (net (code "31") (name "Net-(J3-Pad1)") (class "Default")
      (node (ref "J3") (pin "1") (pinfunction "1_1") (pintype "passive"))
      (node (ref "X22") (pin "1") (pinfunction "1_1") (pintype "passive"))
    )
    (net (code "32") (name "Net-(MD1-+3V3)") (class "Default")
      (node (ref "MD1") (pin "17") (pinfunction "+3V3_17") (pintype "power_in"))
      (node (ref "X30") (pin "1") (pinfunction "1_1") (pintype "passive"))
    )
    (net (code "33") (name "Net-(MD1-A3)") (class "Default")
      (node (ref "MD1") (pin "22") (pinfunction "A3_22") (pintype "bidirectional"))
      (node (ref "X39") (pin "1") (pinfunction "1_1") (pintype "passive"))
    )
    (net (code "34") (name "Net-(MD1-A6)") (class "Default")
      (node (ref "MD1") (pin "25") (pinfunction "A6_25") (pintype "bidirectional"))
      (node (ref "X38") (pin "1") (pinfunction "1_1") (pintype "passive"))
    )
    (net (code "35") (name "Net-(MD1-A7)") (class "Default")
      (node (ref "MD1") (pin "26") (pinfunction "A7_26") (pintype "bidirectional"))
      (node (ref "X37") (pin "1") (pinfunction "1_1") (pintype "passive"))
    )
    (net (code "36") (name "Net-(MD1-D7)") (class "Default")
      (node (ref "MD1") (pin "10") (pinfunction "D7_10") (pintype "bidirectional"))
      (node (ref "X33") (pin "1") (pinfunction "1_1") (pintype "passive"))
    )
    (net (code "37") (name "Net-(MD1-D11{slash}MOSI)") (class "Default")
      (node (ref "MD1") (pin "14") (pinfunction "D11/MOSI_14") (pintype "bidirectional"))
      (node (ref "X34") (pin "1") (pinfunction "1_1") (pintype "passive"))
    )
    (net (code "38") (name "Net-(MD1-D12{slash}MISO)") (class "Default")
      (node (ref "MD1") (pin "15") (pinfunction "D12/MISO_15") (pintype "bidirectional"))
      (node (ref "X35") (pin "1") (pinfunction "1_1") (pintype "passive"))
    )
    (net (code "39") (name "Net-(MD1-D13{slash}SCK)") (class "Default")
      (node (ref "MD1") (pin "16") (pinfunction "D13/SCK_16") (pintype "bidirectional"))
      (node (ref "X36") (pin "1") (pinfunction "1_1") (pintype "passive"))
    )
    (net (code "40") (name "Net-(R1-Pad2)") (class "Default")
      (node (ref "R1") (pin "2") (pinfunction "2_2") (pintype "passive"))
      (node (ref "X4") (pin "2") (pinfunction "2_2") (pintype "passive"))
    )
    (net (code "41") (name "Net-(R2-Pad2)") (class "Default")
      (node (ref "R2") (pin "2") (pinfunction "2_2") (pintype "passive"))
      (node (ref "X7") (pin "2") (pinfunction "2_2") (pintype "passive"))
    )
    (net (code "42") (name "Net-(R3-Pad2)") (class "Default")
      (node (ref "R3") (pin "2") (pinfunction "2_2") (pintype "passive"))
      (node (ref "X8") (pin "2") (pinfunction "2_2") (pintype "passive"))
    )
    (net (code "43") (name "Net-(R4-Pad2)") (class "Default")
      (node (ref "R4") (pin "2") (pinfunction "2_2") (pintype "passive"))
      (node (ref "X9") (pin "2") (pinfunction "2_2") (pintype "passive"))
    )
    (net (code "44") (name "Net-(R5-Pad2)") (class "Default")
      (node (ref "R5") (pin "2") (pinfunction "2_2") (pintype "passive"))
      (node (ref "X16") (pin "2") (pinfunction "2_2") (pintype "passive"))
    )
    (net (code "45") (name "Net-(R6-Pad2)") (class "Default")
      (node (ref "R6") (pin "2") (pinfunction "2_2") (pintype "passive"))
      (node (ref "X17") (pin "2") (pinfunction "2_2") (pintype "passive"))
    )
    (net (code "46") (name "Net-(R7-Pad2)") (class "Default")
      (node (ref "R7") (pin "2") (pinfunction "2_2") (pintype "passive"))
      (node (ref "X18") (pin "2") (pinfunction "2_2") (pintype "passive"))
    )
    (net (code "47") (name "Net-(R8-Pad2)") (class "Default")
      (node (ref "R8") (pin "2") (pinfunction "2_2") (pintype "passive"))
      (node (ref "X19") (pin "2") (pinfunction "2_2") (pintype "passive"))
    )
    (net (code "48") (name "Net-(R9-Pad2)") (class "Default")
      (node (ref "R9") (pin "2") (pinfunction "2_2") (pintype "passive"))
      (node (ref "X20") (pin "2") (pinfunction "2_2") (pintype "passive"))
    )
    (net (code "49") (name "Net-(R10-Pad2)") (class "Default")
      (node (ref "R10") (pin "2") (pinfunction "2_2") (pintype "passive"))
      (node (ref "X21") (pin "2") (pinfunction "2_2") (pintype "passive"))
    )
    (net (code "50") (name "Net-(U3-QC)") (class "Default")
      (node (ref "U3") (pin "2") (pinfunction "QC_2") (pintype "output"))
      (node (ref "X10") (pin "1") (pinfunction "1_1") (pintype "passive"))
    )
    (net (code "51") (name "Net-(U3-QD)") (class "Default")
      (node (ref "U3") (pin "3") (pinfunction "QD_3") (pintype "output"))
      (node (ref "X11") (pin "1") (pinfunction "1_1") (pintype "passive"))
    )
    (net (code "52") (name "Net-(U3-QE)") (class "Default")
      (node (ref "U3") (pin "4") (pinfunction "QE_4") (pintype "output"))
      (node (ref "X12") (pin "1") (pinfunction "1_1") (pintype "passive"))
    )
    (net (code "53") (name "Net-(U3-QF)") (class "Default")
      (node (ref "U3") (pin "5") (pinfunction "QF_5") (pintype "output"))
      (node (ref "X13") (pin "1") (pinfunction "1_1") (pintype "passive"))
    )
    (net (code "54") (name "Net-(U3-QG)") (class "Default")
      (node (ref "U3") (pin "6") (pinfunction "QG_6") (pintype "output"))
      (node (ref "X14") (pin "1") (pinfunction "1_1") (pintype "passive"))
    )
    (net (code "55") (name "Net-(U3-QH)") (class "Default")
      (node (ref "U3") (pin "7") (pinfunction "QH_7") (pintype "output"))
      (node (ref "X15") (pin "1") (pinfunction "1_1") (pintype "passive"))
    )
    (net (code "56") (name "unconnected-(MD1-+5V-Pad27)") (class "Default")
      (node (ref "MD1") (pin "27") (pinfunction "+5V_27") (pintype "power_in"))
    )
    (net (code "57") (name "unconnected-(MD1-AREF-Pad18)") (class "Default")
      (node (ref "MD1") (pin "18") (pinfunction "AREF_18") (pintype "passive+no_connect"))
    )
    (net (code "58") (name "unconnected-(MD1-~{RESET}-Pad28)") (class "Default")
      (node (ref "MD1") (pin "28") (pinfunction "~{RESET}_28") (pintype "input+no_connect"))
    )
    (net (code "59") (name "unconnected-(U2-GPIO2{slash}SDA1-Pad3)") (class "Default")
      (node (ref "U2") (pin "3") (pinfunction "GPIO2/SDA1_3") (pintype "bidirectional"))
    )
    (net (code "60") (name "unconnected-(U2-GPIO3{slash}SCL1-Pad5)") (class "Default")
      (node (ref "U2") (pin "5") (pinfunction "GPIO3/SCL1_5") (pintype "bidirectional"))
    )
    (net (code "61") (name "unconnected-(U2-GPIO4{slash}GPIO_GCKL-Pad7)") (class "Default")
      (node (ref "U2") (pin "7") (pinfunction "GPIO4/GPIO_GCKL_7") (pintype "bidirectional"))
    )
    (net (code "62") (name "unconnected-(U2-GPIO5-Pad29)") (class "Default")
      (node (ref "U2") (pin "29") (pinfunction "GPIO5_29") (pintype "bidirectional"))
    )
    (net (code "63") (name "unconnected-(U2-GPIO6-Pad31)") (class "Default")
      (node (ref "U2") (pin "31") (pinfunction "GPIO6_31") (pintype "bidirectional"))
    )
    (net (code "64") (name "unconnected-(U2-GPIO7{slash}~{SPI_CE1}-Pad26)") (class "Default")
      (node (ref "U2") (pin "26") (pinfunction "GPIO7/~{SPI_CE1}_26") (pintype "bidirectional"))
    )
    (net (code "65") (name "unconnected-(U2-GPIO8{slash}~{SPI_CE0}-Pad24)") (class "Default")
      (node (ref "U2") (pin "24") (pinfunction "GPIO8/~{SPI_CE0}_24") (pintype "bidirectional"))
    )
    (net (code "66") (name "unconnected-(U2-GPIO9{slash}SPI_MISO-Pad21)") (class "Default")
      (node (ref "U2") (pin "21") (pinfunction "GPIO9/SPI_MISO_21") (pintype "bidirectional"))
    )
    (net (code "67") (name "unconnected-(U2-GPIO10{slash}SPI_MOSI-Pad19)") (class "Default")
      (node (ref "U2") (pin "19") (pinfunction "GPIO10/SPI_MOSI_19") (pintype "bidirectional"))
    )
    (net (code "68") (name "unconnected-(U2-GPIO11{slash}SPI_SCLK-Pad23)") (class "Default")
      (node (ref "U2") (pin "23") (pinfunction "GPIO11/SPI_SCLK_23") (pintype "bidirectional"))
    )
    (net (code "69") (name "unconnected-(U2-GPIO12-Pad32)") (class "Default")
      (node (ref "U2") (pin "32") (pinfunction "GPIO12_32") (pintype "bidirectional"))
    )
    (net (code "70") (name "unconnected-(U2-GPIO13-Pad33)") (class "Default")
      (node (ref "U2") (pin "33") (pinfunction "GPIO13_33") (pintype "bidirectional"))
    )
    (net (code "71") (name "unconnected-(U2-GPIO16-Pad36)") (class "Default")
      (node (ref "U2") (pin "36") (pinfunction "GPIO16_36") (pintype "bidirectional"))
    )
    (net (code "72") (name "unconnected-(U2-GPIO17{slash}GPIO_GEN0-Pad11)") (class "Default")
      (node (ref "U2") (pin "11") (pinfunction "GPIO17/GPIO_GEN0_11") (pintype "bidirectional"))
    )
    (net (code "73") (name "unconnected-(U2-GPIO18{slash}GPIO_GEN1-Pad12)") (class "Default")
      (node (ref "U2") (pin "12") (pinfunction "GPIO18/GPIO_GEN1_12") (pintype "bidirectional"))
    )
    (net (code "74") (name "unconnected-(U2-GPIO19-Pad35)") (class "Default")
      (node (ref "U2") (pin "35") (pinfunction "GPIO19_35") (pintype "bidirectional"))
    )
    (net (code "75") (name "unconnected-(U2-GPIO20-Pad38)") (class "Default")
      (node (ref "U2") (pin "38") (pinfunction "GPIO20_38") (pintype "bidirectional"))
    )
    (net (code "76") (name "unconnected-(U2-GPIO21-Pad40)") (class "Default")
      (node (ref "U2") (pin "40") (pinfunction "GPIO21_40") (pintype "bidirectional"))
    )
    (net (code "77") (name "unconnected-(U2-GPIO22{slash}GPIO_GEN3-Pad15)") (class "Default")
      (node (ref "U2") (pin "15") (pinfunction "GPIO22/GPIO_GEN3_15") (pintype "bidirectional"))
    )
    (net (code "78") (name "unconnected-(U2-GPIO23{slash}GPIO_GEN4-Pad16)") (class "Default")
      (node (ref "U2") (pin "16") (pinfunction "GPIO23/GPIO_GEN4_16") (pintype "bidirectional"))
    )
    (net (code "79") (name "unconnected-(U2-GPIO24{slash}GPIO_GEN5-Pad18)") (class "Default")
      (node (ref "U2") (pin "18") (pinfunction "GPIO24/GPIO_GEN5_18") (pintype "bidirectional"))
    )
    (net (code "80") (name "unconnected-(U2-GPIO25{slash}GPIO_GEN6-Pad22)") (class "Default")
      (node (ref "U2") (pin "22") (pinfunction "GPIO25/GPIO_GEN6_22") (pintype "bidirectional"))
    )
    (net (code "81") (name "unconnected-(U2-GPIO26-Pad37)") (class "Default")
      (node (ref "U2") (pin "37") (pinfunction "GPIO26_37") (pintype "bidirectional"))
    )
    (net (code "82") (name "unconnected-(U2-GPIO27{slash}GPIO_GEN2-Pad13)") (class "Default")
      (node (ref "U2") (pin "13") (pinfunction "GPIO27/GPIO_GEN2_13") (pintype "bidirectional"))
    )
    (net (code "83") (name "unconnected-(U2-ID_SC-Pad28)") (class "Default")
      (node (ref "U2") (pin "28") (pinfunction "ID_SC_28") (pintype "bidirectional"))
    )
    (net (code "84") (name "unconnected-(U2-ID_SD-Pad27)") (class "Default")
      (node (ref "U2") (pin "27") (pinfunction "ID_SD_27") (pintype "bidirectional"))
    )
    (net (code "85") (name "unconnected-(X1-Pad3)") (class "Default")
      (node (ref "X1") (pin "3") (pinfunction "3_3") (pintype "passive+no_connect"))
    )
    (net (code "86") (name "unconnected-(X29-Pad1)") (class "Default")
      (node (ref "X29") (pin "1") (pinfunction "1_1") (pintype "passive"))
    )
  )
)
